# CW308T_ATSAML11.net
KiCad netlist of a schematic drawn in Altium Designer
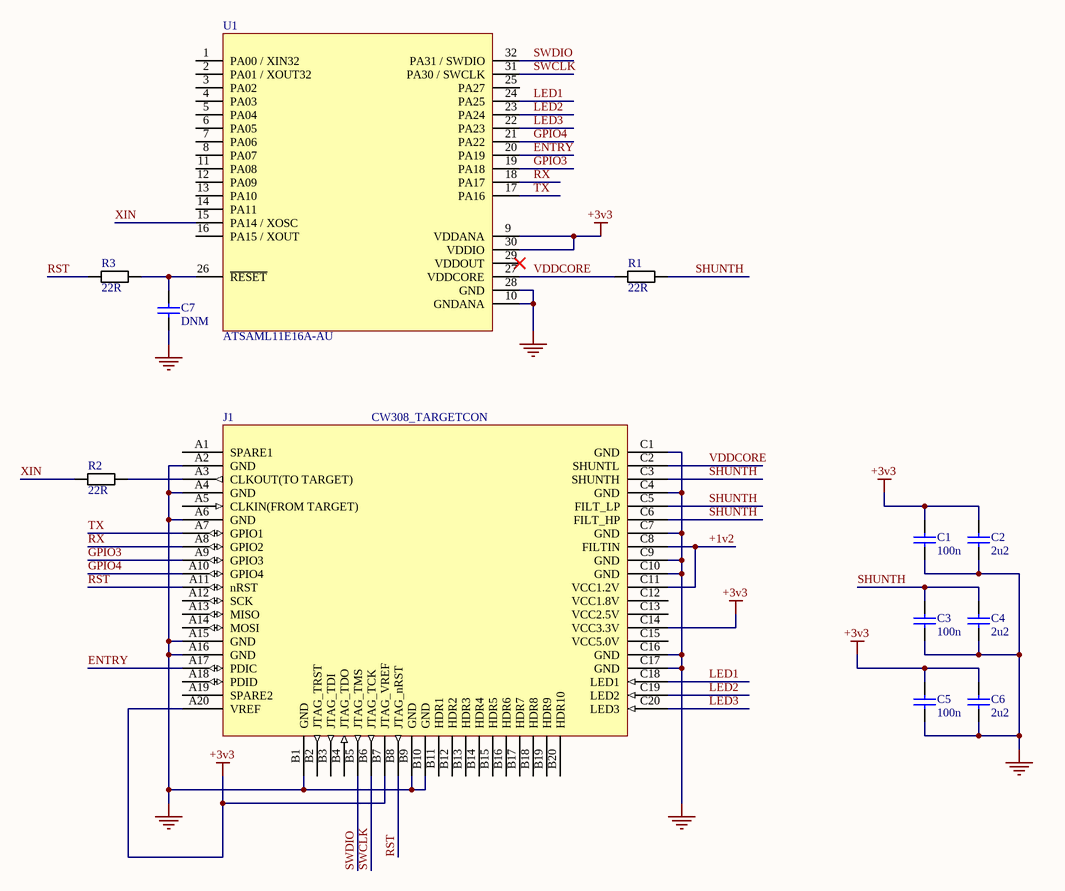
[diagram p0: CW308T_ATSAML11.SchDoc]

(export (version "E")
  (design (tool "Eeschema 10.0.6"))
  (components
    (comp (ref "C1")
      (value "100n")
      (footprint "CAPC0603_M")
      (description "100n, 0603")
      (fields (field (name "PART NUMBER") "CCHIP-100n-0603"))
      (libsource (lib "NewAE_AltiumLib") (part "CAP"))
    )
    (comp (ref "C2")
      (value "2u2")
      (footprint "CAPC0603_M")
      (description "2u2, 0603")
      (fields (field (name "PART NUMBER") "CCHIP-2u2-0603"))
      (libsource (lib "NewAE_AltiumLib") (part "CAP"))
    )
    (comp (ref "C3")
      (value "100n")
      (footprint "CAPC0603_M")
      (description "100n, 0603")
      (fields (field (name "PART NUMBER") "CCHIP-100n-0603"))
      (libsource (lib "NewAE_AltiumLib") (part "CAP"))
    )
    (comp (ref "C4")
      (value "2u2")
      (footprint "CAPC0603_M")
      (description "2u2, 0603")
      (fields (field (name "PART NUMBER") "CCHIP-2u2-0603"))
      (libsource (lib "NewAE_AltiumLib") (part "CAP"))
    )
    (comp (ref "C5")
      (value "100n")
      (footprint "CAPC0603_M")
      (description "100n, 0603")
      (fields (field (name "PART NUMBER") "CCHIP-100n-0603"))
      (libsource (lib "NewAE_AltiumLib") (part "CAP"))
    )
    (comp (ref "C6")
      (value "2u2")
      (footprint "CAPC0603_M")
      (description "2u2, 0603")
      (fields (field (name "PART NUMBER") "CCHIP-2u2-0603"))
      (libsource (lib "NewAE_AltiumLib") (part "CAP"))
    )
    (comp (ref "C7")
      (value "DNM")
      (footprint "CAPC0603_M")
      (fields (field (name "PART NUMBER") "CCHIP-100n-0603"))
      (libsource (lib "NewAE_AltiumLib") (part "CAP"))
    )
    (comp (ref "J1")
      (value "CW308_TARGETCON")
      (footprint "CW308_TBOARD_CONN")
      (description "CW308 \"Standard\" Target Board Connector")
      (fields (field (name "PART NUMBER") "CW308_TBOARD"))
      (libsource (lib "NewAE_AltiumLib") (part "CW308_TBOARD"))
    )
    (comp (ref "R1")
      (value "22R")
      (footprint "RESC1608X55N")
      (description "22R res, 0603, 1%, 1/10W")
      (fields (field (name "PART NUMBER") "RCHIP-22R-0603") (field (name "TOLERANCE") "1%"))
      (libsource (lib "NewAE_AltiumLib") (part "RES-EU"))
    )
    (comp (ref "R2")
      (value "22R")
      (footprint "RESC1608X55N")
      (description "22R res, 0603, 1%, 1/10W")
      (fields (field (name "PART NUMBER") "RCHIP-22R-0603") (field (name "TOLERANCE") "1%"))
      (libsource (lib "NewAE_AltiumLib") (part "RES-EU"))
    )
    (comp (ref "R3")
      (value "22R")
      (footprint "RESC1608X55N")
      (description "22R res, 0603, 1%, 1/10W")
      (fields (field (name "PART NUMBER") "RCHIP-22R-0603") (field (name "TOLERANCE") "1%"))
      (libsource (lib "NewAE_AltiumLib") (part "RES-EU"))
    )
    (comp (ref "U1") (value "ATSAML11E16A-AU") (libsource (lib "NewAE_AltiumLib") (part "ATSAML11E16A-AU")))
  )
  (nets
    (net (code "1") (name "+3v3") (class "Default")
      (node (ref "C1") (pin "1") (pinfunction "1_1") (pintype "passive"))
      (node (ref "C2") (pin "1") (pinfunction "1_1") (pintype "passive"))
      (node (ref "C5") (pin "1") (pinfunction "1_1") (pintype "passive"))
      (node (ref "C6") (pin "1") (pinfunction "1_1") (pintype "passive"))
      (node (ref "J1") (pin "A20") (pinfunction "VREF_A20") (pintype "tri_state"))
      (node (ref "J1") (pin "B7") (pinfunction "JTAG_VREF_B7") (pintype "tri_state"))
      (node (ref "J1") (pin "C14") (pinfunction "VCC3.3V_C14") (pintype "power_in"))
      (node (ref "U1") (pin "30") (pinfunction "VDDIO_30") (pintype "passive"))
      (node (ref "U1") (pin "9") (pinfunction "VDDANA_9") (pintype "passive"))
    )
    (net (code "2") (name "/+1v2") (class "Default")
      (node (ref "J1") (pin "C11") (pinfunction "VCC1.2V_C11") (pintype "power_in"))
      (node (ref "J1") (pin "C8") (pinfunction "FILTIN_C8") (pintype "passive"))
    )
    (net (code "3") (name "/ENTRY") (class "Default")
      (node (ref "J1") (pin "A17") (pinfunction "PDIC_A17") (pintype "bidirectional"))
      (node (ref "U1") (pin "20") (pinfunction "PA19_20") (pintype "passive"))
    )
    (net (code "4") (name "/GPIO3") (class "Default")
      (node (ref "J1") (pin "A9") (pinfunction "GPIO3_A9") (pintype "bidirectional"))
      (node (ref "U1") (pin "19") (pinfunction "PA18_19") (pintype "passive"))
    )
    (net (code "5") (name "/GPIO4") (class "Default")
      (node (ref "J1") (pin "A10") (pinfunction "GPIO4_A10") (pintype "bidirectional"))
      (node (ref "U1") (pin "21") (pinfunction "PA22_21") (pintype "passive"))
    )
    (net (code "6") (name "/LED1") (class "Default")
      (node (ref "J1") (pin "C18") (pinfunction "LED1_C18") (pintype "input"))
      (node (ref "U1") (pin "24") (pinfunction "PA25_24") (pintype "passive"))
    )
    (net (code "7") (name "/LED2") (class "Default")
      (node (ref "J1") (pin "C19") (pinfunction "LED2_C19") (pintype "input"))
      (node (ref "U1") (pin "23") (pinfunction "PA24_23") (pintype "passive"))
    )
    (net (code "8") (name "/LED3") (class "Default")
      (node (ref "J1") (pin "C20") (pinfunction "LED3_C20") (pintype "input"))
      (node (ref "U1") (pin "22") (pinfunction "PA23_22") (pintype "passive"))
    )
    (net (code "9") (name "/RST") (class "Default")
      (node (ref "J1") (pin "A11") (pinfunction "nRST_A11") (pintype "bidirectional"))
      (node (ref "J1") (pin "B8") (pinfunction "JTAG_nRST_B8") (pintype "output"))
      (node (ref "R3") (pin "1") (pinfunction "1_1") (pintype "passive"))
    )
    (net (code "10") (name "/RX") (class "Default")
      (node (ref "J1") (pin "A8") (pinfunction "GPIO2_A8") (pintype "bidirectional"))
      (node (ref "U1") (pin "18") (pinfunction "PA17_18") (pintype "passive"))
    )
    (net (code "11") (name "/SHUNTH") (class "Default")
      (node (ref "C3") (pin "1") (pinfunction "1_1") (pintype "passive"))
      (node (ref "C4") (pin "1") (pinfunction "1_1") (pintype "passive"))
      (node (ref "J1") (pin "C3") (pinfunction "SHUNTH_C3") (pintype "passive"))
      (node (ref "J1") (pin "C5") (pinfunction "FILT_LP_C5") (pintype "passive"))
      (node (ref "J1") (pin "C6") (pinfunction "FILT_HP_C6") (pintype "passive"))
      (node (ref "R1") (pin "2") (pinfunction "2_2") (pintype "passive"))
    )
    (net (code "12") (name "/SWCLK") (class "Default")
      (node (ref "J1") (pin "B6") (pinfunction "JTAG_TCK_B6") (pintype "output"))
      (node (ref "U1") (pin "31") (pinfunction "PA30_/_SWCLK_31") (pintype "passive"))
    )
    (net (code "13") (name "/SWDIO") (class "Default")
      (node (ref "J1") (pin "B5") (pinfunction "JTAG_TMS_B5") (pintype "output"))
      (node (ref "U1") (pin "32") (pinfunction "PA31_/_SWDIO_32") (pintype "passive"))
    )
    (net (code "14") (name "/TX") (class "Default")
      (node (ref "J1") (pin "A7") (pinfunction "GPIO1_A7") (pintype "bidirectional"))
      (node (ref "U1") (pin "17") (pinfunction "PA16_17") (pintype "passive"))
    )
    (net (code "15") (name "/VDDCORE") (class "Default")
      (node (ref "J1") (pin "C2") (pinfunction "SHUNTL_C2") (pintype "passive"))
      (node (ref "R1") (pin "1") (pinfunction "1_1") (pintype "passive"))
      (node (ref "U1") (pin "27") (pinfunction "VDDCORE_27") (pintype "passive"))
    )
    (net (code "16") (name "/XIN") (class "Default")
      (node (ref "R2") (pin "1") (pinfunction "1_1") (pintype "passive"))
      (node (ref "U1") (pin "15") (pinfunction "PA14_/_XOSC_15") (pintype "passive"))
    )
    (net (code "17") (name "GND") (class "Default")
      (node (ref "C1") (pin "2") (pinfunction "2_2") (pintype "passive"))
      (node (ref "C2") (pin "2") (pinfunction "2_2") (pintype "passive"))
      (node (ref "C3") (pin "2") (pinfunction "2_2") (pintype "passive"))
      (node (ref "C4") (pin "2") (pinfunction "2_2") (pintype "passive"))
      (node (ref "C5") (pin "2") (pinfunction "2_2") (pintype "passive"))
      (node (ref "C6") (pin "2") (pinfunction "2_2") (pintype "passive"))
      (node (ref "C7") (pin "2") (pinfunction "2_2") (pintype "passive"))
      (node (ref "J1") (pin "A15") (pinfunction "GND_A15") (pintype "passive"))
      (node (ref "J1") (pin "A16") (pinfunction "GND_A16") (pintype "passive"))
      (node (ref "J1") (pin "A2") (pinfunction "GND_A2") (pintype "passive"))
      (node (ref "J1") (pin "A4") (pinfunction "GND_A4") (pintype "passive"))
      (node (ref "J1") (pin "A6") (pinfunction "GND_A6") (pintype "power_in"))
      (node (ref "J1") (pin "B1") (pinfunction "GND_B1") (pintype "passive"))
      (node (ref "J1") (pin "B10") (pinfunction "GND_B10") (pintype "passive"))
      (node (ref "J1") (pin "B9") (pinfunction "GND_B9") (pintype "passive"))
      (node (ref "J1") (pin "C1") (pinfunction "GND_C1") (pintype "power_in"))
      (node (ref "J1") (pin "C10") (pinfunction "GND_C10") (pintype "power_in"))
      (node (ref "J1") (pin "C16") (pinfunction "GND_C16") (pintype "power_in"))
      (node (ref "J1") (pin "C17") (pinfunction "GND_C17") (pintype "power_in"))
      (node (ref "J1") (pin "C4") (pinfunction "GND_C4") (pintype "power_in"))
      (node (ref "J1") (pin "C7") (pinfunction "GND_C7") (pintype "power_in"))
      (node (ref "J1") (pin "C9") (pinfunction "GND_C9") (pintype "power_in"))
      (node (ref "U1") (pin "10") (pinfunction "GNDANA_10") (pintype "passive"))
      (node (ref "U1") (pin "28") (pinfunction "GND_28") (pintype "passive"))
    )
    (net (code "18") (name "Net-(J1-CLKOUT(TO_TARGET))") (class "Default")
      (node (ref "J1") (pin "A3") (pinfunction "CLKOUT(TO_TARGET)_A3") (pintype "output"))
      (node (ref "R2") (pin "2") (pinfunction "2_2") (pintype "passive"))
    )
    (net (code "19") (name "Net-(U1-~{RESET})") (class "Default")
      (node (ref "C7") (pin "1") (pinfunction "1_1") (pintype "passive"))
      (node (ref "R3") (pin "2") (pinfunction "2_2") (pintype "passive"))
      (node (ref "U1") (pin "26") (pinfunction "~{RESET}_26") (pintype "passive"))
    )
    (net (code "20") (name "unconnected-(J1-CLKIN(FROM_TARGET)-PadA5)") (class "Default")
      (node (ref "J1") (pin "A5") (pinfunction "CLKIN(FROM_TARGET)_A5") (pintype "input"))
    )
    (net (code "21") (name "unconnected-(J1-HDR1-PadB11)") (class "Default")
      (node (ref "J1") (pin "B11") (pinfunction "HDR1_B11") (pintype "passive"))
    )
    (net (code "22") (name "unconnected-(J1-HDR2-PadB12)") (class "Default")
      (node (ref "J1") (pin "B12") (pinfunction "HDR2_B12") (pintype "passive"))
    )
    (net (code "23") (name "unconnected-(J1-HDR3-PadB13)") (class "Default")
      (node (ref "J1") (pin "B13") (pinfunction "HDR3_B13") (pintype "passive"))
    )
    (net (code "24") (name "unconnected-(J1-HDR4-PadB14)") (class "Default")
      (node (ref "J1") (pin "B14") (pinfunction "HDR4_B14") (pintype "passive"))
    )
    (net (code "25") (name "unconnected-(J1-HDR5-PadB15)") (class "Default")
      (node (ref "J1") (pin "B15") (pinfunction "HDR5_B15") (pintype "passive"))
    )
    (net (code "26") (name "unconnected-(J1-HDR6-PadB16)") (class "Default")
      (node (ref "J1") (pin "B16") (pinfunction "HDR6_B16") (pintype "passive"))
    )
    (net (code "27") (name "unconnected-(J1-HDR7-PadB17)") (class "Default")
      (node (ref "J1") (pin "B17") (pinfunction "HDR7_B17") (pintype "passive"))
    )
    (net (code "28") (name "unconnected-(J1-HDR8-PadB18)") (class "Default")
      (node (ref "J1") (pin "B18") (pinfunction "HDR8_B18") (pintype "passive"))
    )
    (net (code "29") (name "unconnected-(J1-HDR9-PadB19)") (class "Default")
      (node (ref "J1") (pin "B19") (pinfunction "HDR9_B19") (pintype "passive"))
    )
    (net (code "30") (name "unconnected-(J1-HDR10-PadB20)") (class "Default")
      (node (ref "J1") (pin "B20") (pinfunction "HDR10_B20") (pintype "passive"))
    )
    (net (code "31") (name "unconnected-(J1-JTAG_TDI-PadB3)") (class "Default")
      (node (ref "J1") (pin "B3") (pinfunction "JTAG_TDI_B3") (pintype "output"))
    )
    (net (code "32") (name "unconnected-(J1-JTAG_TDO-PadB4)") (class "Default")
      (node (ref "J1") (pin "B4") (pinfunction "JTAG_TDO_B4") (pintype "input"))
    )
    (net (code "33") (name "unconnected-(J1-JTAG_TRST-PadB2)") (class "Default")
      (node (ref "J1") (pin "B2") (pinfunction "JTAG_TRST_B2") (pintype "output"))
    )
    (net (code "34") (name "unconnected-(J1-MISO-PadA13)") (class "Default")
      (node (ref "J1") (pin "A13") (pinfunction "MISO_A13") (pintype "bidirectional"))
    )
    (net (code "35") (name "unconnected-(J1-MOSI-PadA14)") (class "Default")
      (node (ref "J1") (pin "A14") (pinfunction "MOSI_A14") (pintype "bidirectional"))
    )
    (net (code "36") (name "unconnected-(J1-PDID-PadA18)") (class "Default")
      (node (ref "J1") (pin "A18") (pinfunction "PDID_A18") (pintype "bidirectional"))
    )
    (net (code "37") (name "unconnected-(J1-SCK-PadA12)") (class "Default")
      (node (ref "J1") (pin "A12") (pinfunction "SCK_A12") (pintype "bidirectional"))
    )
    (net (code "38") (name "unconnected-(J1-SPARE1-PadA1)") (class "Default")
      (node (ref "J1") (pin "A1") (pinfunction "SPARE1_A1") (pintype "passive"))
    )
    (net (code "39") (name "unconnected-(J1-SPARE2-PadA19)") (class "Default")
      (node (ref "J1") (pin "A19") (pinfunction "SPARE2_A19") (pintype "passive"))
    )
    (net (code "40") (name "unconnected-(J1-VCC1.8V-PadC12)") (class "Default")
      (node (ref "J1") (pin "C12") (pinfunction "VCC1.8V_C12") (pintype "power_in"))
    )
    (net (code "41") (name "unconnected-(J1-VCC2.5V-PadC13)") (class "Default")
      (node (ref "J1") (pin "C13") (pinfunction "VCC2.5V_C13") (pintype "power_in"))
    )
    (net (code "42") (name "unconnected-(J1-VCC5.0V-PadC15)") (class "Default")
      (node (ref "J1") (pin "C15") (pinfunction "VCC5.0V_C15") (pintype "power_in"))
    )
    (net (code "43") (name "unconnected-(U1-PA00_{slash}_XIN32-Pad1)") (class "Default")
      (node (ref "U1") (pin "1") (pinfunction "PA00_/_XIN32_1") (pintype "passive"))
    )
    (net (code "44") (name "unconnected-(U1-PA01_{slash}_XOUT32-Pad2)") (class "Default")
      (node (ref "U1") (pin "2") (pinfunction "PA01_/_XOUT32_2") (pintype "passive"))
    )
    (net (code "45") (name "unconnected-(U1-PA02-Pad3)") (class "Default")
      (node (ref "U1") (pin "3") (pinfunction "PA02_3") (pintype "passive"))
    )
    (net (code "46") (name "unconnected-(U1-PA03-Pad4)") (class "Default")
      (node (ref "U1") (pin "4") (pinfunction "PA03_4") (pintype "passive"))
    )
    (net (code "47") (name "unconnected-(U1-PA04-Pad5)") (class "Default")
      (node (ref "U1") (pin "5") (pinfunction "PA04_5") (pintype "passive"))
    )
    (net (code "48") (name "unconnected-(U1-PA05-Pad6)") (class "Default")
      (node (ref "U1") (pin "6") (pinfunction "PA05_6") (pintype "passive"))
    )
    (net (code "49") (name "unconnected-(U1-PA06-Pad7)") (class "Default")
      (node (ref "U1") (pin "7") (pinfunction "PA06_7") (pintype "passive"))
    )
    (net (code "50") (name "unconnected-(U1-PA07-Pad8)") (class "Default")
      (node (ref "U1") (pin "8") (pinfunction "PA07_8") (pintype "passive"))
    )
    (net (code "51") (name "unconnected-(U1-PA08-Pad11)") (class "Default")
      (node (ref "U1") (pin "11") (pinfunction "PA08_11") (pintype "passive"))
    )
    (net (code "52") (name "unconnected-(U1-PA09-Pad12)") (class "Default")
      (node (ref "U1") (pin "12") (pinfunction "PA09_12") (pintype "passive"))
    )
    (net (code "53") (name "unconnected-(U1-PA10-Pad13)") (class "Default")
      (node (ref "U1") (pin "13") (pinfunction "PA10_13") (pintype "passive"))
    )
    (net (code "54") (name "unconnected-(U1-PA11-Pad14)") (class "Default")
      (node (ref "U1") (pin "14") (pinfunction "PA11_14") (pintype "passive"))
    )
    (net (code "55") (name "unconnected-(U1-PA15_{slash}_XOUT-Pad16)") (class "Default")
      (node (ref "U1") (pin "16") (pinfunction "PA15_/_XOUT_16") (pintype "passive"))
    )
    (net (code "56") (name "unconnected-(U1-PA27-Pad25)") (class "Default")
      (node (ref "U1") (pin "25") (pinfunction "PA27_25") (pintype "passive"))
    )
    (net (code "57") (name "unconnected-(U1-VDDOUT-Pad29)") (class "Default")
      (node (ref "U1") (pin "29") (pinfunction "VDDOUT_29") (pintype "passive+no_connect"))
    )
  )
)
